# CON_Board_v1.net
KiCad netlist of a schematic drawn in EAGLE
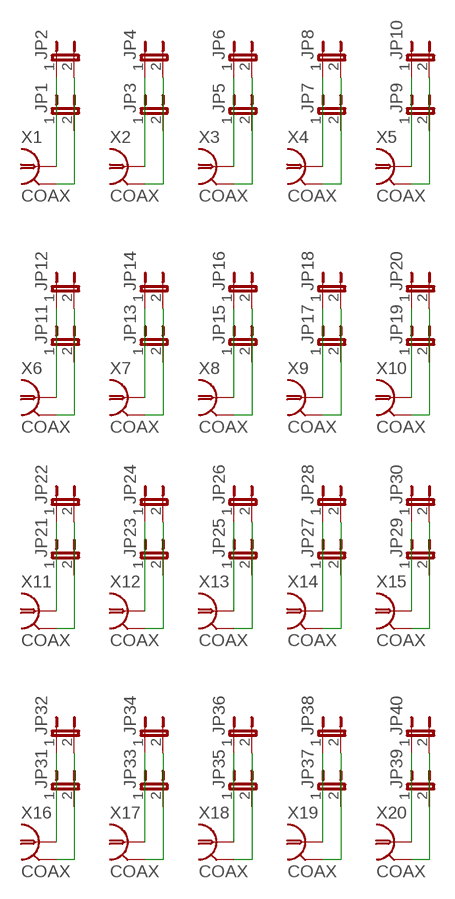
[diagram p0: schematic, sheet 1]

(export (version "E")
  (design (tool "Eeschema 10.0.6"))
  (components
    (comp (ref "JP1")
      (value "JP1E")
      (footprint "eagle-import:JP1")
      (libsource (lib "eagle-import") (part "JP1E"))
    )
    (comp (ref "JP2")
      (value "JP1E")
      (footprint "eagle-import:JP1")
      (libsource (lib "eagle-import") (part "JP1E"))
    )
    (comp (ref "JP3")
      (value "JP1E")
      (footprint "eagle-import:JP1")
      (libsource (lib "eagle-import") (part "JP1E"))
    )
    (comp (ref "JP4")
      (value "JP1E")
      (footprint "eagle-import:JP1")
      (libsource (lib "eagle-import") (part "JP1E"))
    )
    (comp (ref "JP5")
      (value "JP1E")
      (footprint "eagle-import:JP1")
      (libsource (lib "eagle-import") (part "JP1E"))
    )
    (comp (ref "JP6")
      (value "JP1E")
      (footprint "eagle-import:JP1")
      (libsource (lib "eagle-import") (part "JP1E"))
    )
    (comp (ref "JP7")
      (value "JP1E")
      (footprint "eagle-import:JP1")
      (libsource (lib "eagle-import") (part "JP1E"))
    )
    (comp (ref "JP8")
      (value "JP1E")
      (footprint "eagle-import:JP1")
      (libsource (lib "eagle-import") (part "JP1E"))
    )
    (comp (ref "JP9")
      (value "JP1E")
      (footprint "eagle-import:JP1")
      (libsource (lib "eagle-import") (part "JP1E"))
    )
    (comp (ref "JP10")
      (value "JP1E")
      (footprint "eagle-import:JP1")
      (libsource (lib "eagle-import") (part "JP1E"))
    )
    (comp (ref "JP11")
      (value "JP1E")
      (footprint "eagle-import:JP1")
      (libsource (lib "eagle-import") (part "JP1E"))
    )
    (comp (ref "JP12")
      (value "JP1E")
      (footprint "eagle-import:JP1")
      (libsource (lib "eagle-import") (part "JP1E"))
    )
    (comp (ref "JP13")
      (value "JP1E")
      (footprint "eagle-import:JP1")
      (libsource (lib "eagle-import") (part "JP1E"))
    )
    (comp (ref "JP14")
      (value "JP1E")
      (footprint "eagle-import:JP1")
      (libsource (lib "eagle-import") (part "JP1E"))
    )
    (comp (ref "JP15")
      (value "JP1E")
      (footprint "eagle-import:JP1")
      (libsource (lib "eagle-import") (part "JP1E"))
    )
    (comp (ref "JP16")
      (value "JP1E")
      (footprint "eagle-import:JP1")
      (libsource (lib "eagle-import") (part "JP1E"))
    )
    (comp (ref "JP17")
      (value "JP1E")
      (footprint "eagle-import:JP1")
      (libsource (lib "eagle-import") (part "JP1E"))
    )
    (comp (ref "JP18")
      (value "JP1E")
      (footprint "eagle-import:JP1")
      (libsource (lib "eagle-import") (part "JP1E"))
    )
    (comp (ref "JP19")
      (value "JP1E")
      (footprint "eagle-import:JP1")
      (libsource (lib "eagle-import") (part "JP1E"))
    )
    (comp (ref "JP20")
      (value "JP1E")
      (footprint "eagle-import:JP1")
      (libsource (lib "eagle-import") (part "JP1E"))
    )
    (comp (ref "JP21")
      (value "JP1E")
      (footprint "eagle-import:JP1")
      (libsource (lib "eagle-import") (part "JP1E"))
    )
    (comp (ref "JP22")
      (value "JP1E")
      (footprint "eagle-import:JP1")
      (libsource (lib "eagle-import") (part "JP1E"))
    )
    (comp (ref "JP23")
      (value "JP1E")
      (footprint "eagle-import:JP1")
      (libsource (lib "eagle-import") (part "JP1E"))
    )
    (comp (ref "JP24")
      (value "JP1E")
      (footprint "eagle-import:JP1")
      (libsource (lib "eagle-import") (part "JP1E"))
    )
    (comp (ref "JP25")
      (value "JP1E")
      (footprint "eagle-import:JP1")
      (libsource (lib "eagle-import") (part "JP1E"))
    )
    (comp (ref "JP26")
      (value "JP1E")
      (footprint "eagle-import:JP1")
      (libsource (lib "eagle-import") (part "JP1E"))
    )
    (comp (ref "JP27")
      (value "JP1E")
      (footprint "eagle-import:JP1")
      (libsource (lib "eagle-import") (part "JP1E"))
    )
    (comp (ref "JP28")
      (value "JP1E")
      (footprint "eagle-import:JP1")
      (libsource (lib "eagle-import") (part "JP1E"))
    )
    (comp (ref "JP29")
      (value "JP1E")
      (footprint "eagle-import:JP1")
      (libsource (lib "eagle-import") (part "JP1E"))
    )
    (comp (ref "JP30")
      (value "JP1E")
      (footprint "eagle-import:JP1")
      (libsource (lib "eagle-import") (part "JP1E"))
    )
    (comp (ref "JP31")
      (value "JP1E")
      (footprint "eagle-import:JP1")
      (libsource (lib "eagle-import") (part "JP1E"))
    )
    (comp (ref "JP32")
      (value "JP1E")
      (footprint "eagle-import:JP1")
      (libsource (lib "eagle-import") (part "JP1E"))
    )
    (comp (ref "JP33")
      (value "JP1E")
      (footprint "eagle-import:JP1")
      (libsource (lib "eagle-import") (part "JP1E"))
    )
    (comp (ref "JP34")
      (value "JP1E")
      (footprint "eagle-import:JP1")
      (libsource (lib "eagle-import") (part "JP1E"))
    )
    (comp (ref "JP35")
      (value "JP1E")
      (footprint "eagle-import:JP1")
      (libsource (lib "eagle-import") (part "JP1E"))
    )
    (comp (ref "JP36")
      (value "JP1E")
      (footprint "eagle-import:JP1")
      (libsource (lib "eagle-import") (part "JP1E"))
    )
    (comp (ref "JP37")
      (value "JP1E")
      (footprint "eagle-import:JP1")
      (libsource (lib "eagle-import") (part "JP1E"))
    )
    (comp (ref "JP38")
      (value "JP1E")
      (footprint "eagle-import:JP1")
      (libsource (lib "eagle-import") (part "JP1E"))
    )
    (comp (ref "JP39")
      (value "JP1E")
      (footprint "eagle-import:JP1")
      (libsource (lib "eagle-import") (part "JP1E"))
    )
    (comp (ref "JP40")
      (value "JP1E")
      (footprint "eagle-import:JP1")
      (libsource (lib "eagle-import") (part "JP1E"))
    )
    (comp (ref "X1")
      (value "COAX")
      (footprint "eagle-import:31-5329")
      (libsource (lib "eagle-import") (part "31-5329-52RFX31-5329-52RFX"))
    )
    (comp (ref "X2")
      (value "COAX")
      (footprint "eagle-import:31-5329")
      (libsource (lib "eagle-import") (part "31-5329-52RFX31-5329-52RFX"))
    )
    (comp (ref "X3")
      (value "COAX")
      (footprint "eagle-import:31-5329")
      (libsource (lib "eagle-import") (part "31-5329-52RFX31-5329-52RFX"))
    )
    (comp (ref "X4")
      (value "COAX")
      (footprint "eagle-import:31-5329")
      (libsource (lib "eagle-import") (part "31-5329-52RFX31-5329-52RFX"))
    )
    (comp (ref "X5")
      (value "COAX")
      (footprint "eagle-import:31-5329")
      (libsource (lib "eagle-import") (part "31-5329-52RFX31-5329-52RFX"))
    )
    (comp (ref "X6")
      (value "COAX")
      (footprint "eagle-import:31-5329")
      (libsource (lib "eagle-import") (part "31-5329-52RFX31-5329-52RFX"))
    )
    (comp (ref "X7")
      (value "COAX")
      (footprint "eagle-import:31-5329")
      (libsource (lib "eagle-import") (part "31-5329-52RFX31-5329-52RFX"))
    )
    (comp (ref "X8")
      (value "COAX")
      (footprint "eagle-import:31-5329")
      (libsource (lib "eagle-import") (part "31-5329-52RFX31-5329-52RFX"))
    )
    (comp (ref "X9")
      (value "COAX")
      (footprint "eagle-import:31-5329")
      (libsource (lib "eagle-import") (part "31-5329-52RFX31-5329-52RFX"))
    )
    (comp (ref "X10")
      (value "COAX")
      (footprint "eagle-import:31-5329")
      (libsource (lib "eagle-import") (part "31-5329-52RFX31-5329-52RFX"))
    )
    (comp (ref "X11")
      (value "COAX")
      (footprint "eagle-import:31-5329")
      (libsource (lib "eagle-import") (part "31-5329-52RFX31-5329-52RFX"))
    )
    (comp (ref "X12")
      (value "COAX")
      (footprint "eagle-import:31-5329")
      (libsource (lib "eagle-import") (part "31-5329-52RFX31-5329-52RFX"))
    )
    (comp (ref "X13")
      (value "COAX")
      (footprint "eagle-import:31-5329")
      (libsource (lib "eagle-import") (part "31-5329-52RFX31-5329-52RFX"))
    )
    (comp (ref "X14")
      (value "COAX")
      (footprint "eagle-import:31-5329")
      (libsource (lib "eagle-import") (part "31-5329-52RFX31-5329-52RFX"))
    )
    (comp (ref "X15")
      (value "COAX")
      (footprint "eagle-import:31-5329")
      (libsource (lib "eagle-import") (part "31-5329-52RFX31-5329-52RFX"))
    )
    (comp (ref "X16")
      (value "COAX")
      (footprint "eagle-import:31-5329")
      (libsource (lib "eagle-import") (part "31-5329-52RFX31-5329-52RFX"))
    )
    (comp (ref "X17")
      (value "COAX")
      (footprint "eagle-import:31-5329")
      (libsource (lib "eagle-import") (part "31-5329-52RFX31-5329-52RFX"))
    )
    (comp (ref "X18")
      (value "COAX")
      (footprint "eagle-import:31-5329")
      (libsource (lib "eagle-import") (part "31-5329-52RFX31-5329-52RFX"))
    )
    (comp (ref "X19")
      (value "COAX")
      (footprint "eagle-import:31-5329")
      (libsource (lib "eagle-import") (part "31-5329-52RFX31-5329-52RFX"))
    )
    (comp (ref "X20")
      (value "COAX")
      (footprint "eagle-import:31-5329")
      (libsource (lib "eagle-import") (part "31-5329-52RFX31-5329-52RFX"))
    )
  )
  (nets
    (net (code "1") (name "Net-(JP1-Pad1)") (class "Default")
      (node (ref "JP1") (pin "1") (pinfunction "1_1") (pintype "passive"))
      (node (ref "JP2") (pin "1") (pinfunction "1_1") (pintype "passive"))
      (node (ref "X1") (pin "1") (pinfunction "1_1") (pintype "passive"))
    )
    (net (code "2") (name "Net-(JP1-Pad2)") (class "Default")
      (node (ref "JP1") (pin "2") (pinfunction "2_2") (pintype "passive"))
      (node (ref "JP2") (pin "2") (pinfunction "2_2") (pintype "passive"))
      (node (ref "X1") (pin "2") (pinfunction "2_2") (pintype "passive"))
      (node (ref "X1") (pin "3") (pinfunction "2_3") (pintype "passive"))
      (node (ref "X1") (pin "4") (pinfunction "2_4") (pintype "passive"))
      (node (ref "X1") (pin "5") (pinfunction "2_5") (pintype "passive"))
    )
    (net (code "3") (name "Net-(JP3-Pad1)") (class "Default")
      (node (ref "JP3") (pin "1") (pinfunction "1_1") (pintype "passive"))
      (node (ref "JP4") (pin "1") (pinfunction "1_1") (pintype "passive"))
      (node (ref "X2") (pin "1") (pinfunction "1_1") (pintype "passive"))
    )
    (net (code "4") (name "Net-(JP3-Pad2)") (class "Default")
      (node (ref "JP3") (pin "2") (pinfunction "2_2") (pintype "passive"))
      (node (ref "JP4") (pin "2") (pinfunction "2_2") (pintype "passive"))
      (node (ref "X2") (pin "2") (pinfunction "2_2") (pintype "passive"))
      (node (ref "X2") (pin "3") (pinfunction "2_3") (pintype "passive"))
      (node (ref "X2") (pin "4") (pinfunction "2_4") (pintype "passive"))
      (node (ref "X2") (pin "5") (pinfunction "2_5") (pintype "passive"))
    )
    (net (code "5") (name "Net-(JP5-Pad1)") (class "Default")
      (node (ref "JP5") (pin "1") (pinfunction "1_1") (pintype "passive"))
      (node (ref "JP6") (pin "1") (pinfunction "1_1") (pintype "passive"))
      (node (ref "X3") (pin "1") (pinfunction "1_1") (pintype "passive"))
    )
    (net (code "6") (name "Net-(JP5-Pad2)") (class "Default")
      (node (ref "JP5") (pin "2") (pinfunction "2_2") (pintype "passive"))
      (node (ref "JP6") (pin "2") (pinfunction "2_2") (pintype "passive"))
      (node (ref "X3") (pin "2") (pinfunction "2_2") (pintype "passive"))
      (node (ref "X3") (pin "3") (pinfunction "2_3") (pintype "passive"))
      (node (ref "X3") (pin "4") (pinfunction "2_4") (pintype "passive"))
      (node (ref "X3") (pin "5") (pinfunction "2_5") (pintype "passive"))
    )
    (net (code "7") (name "Net-(JP7-Pad1)") (class "Default")
      (node (ref "JP7") (pin "1") (pinfunction "1_1") (pintype "passive"))
      (node (ref "JP8") (pin "1") (pinfunction "1_1") (pintype "passive"))
      (node (ref "X4") (pin "1") (pinfunction "1_1") (pintype "passive"))
    )
    (net (code "8") (name "Net-(JP7-Pad2)") (class "Default")
      (node (ref "JP7") (pin "2") (pinfunction "2_2") (pintype "passive"))
      (node (ref "JP8") (pin "2") (pinfunction "2_2") (pintype "passive"))
      (node (ref "X4") (pin "2") (pinfunction "2_2") (pintype "passive"))
      (node (ref "X4") (pin "3") (pinfunction "2_3") (pintype "passive"))
      (node (ref "X4") (pin "4") (pinfunction "2_4") (pintype "passive"))
      (node (ref "X4") (pin "5") (pinfunction "2_5") (pintype "passive"))
    )
    (net (code "9") (name "Net-(JP10-Pad1)") (class "Default")
      (node (ref "JP10") (pin "1") (pinfunction "1_1") (pintype "passive"))
      (node (ref "JP9") (pin "1") (pinfunction "1_1") (pintype "passive"))
      (node (ref "X5") (pin "1") (pinfunction "1_1") (pintype "passive"))
    )
    (net (code "10") (name "Net-(JP10-Pad2)") (class "Default")
      (node (ref "JP10") (pin "2") (pinfunction "2_2") (pintype "passive"))
      (node (ref "JP9") (pin "2") (pinfunction "2_2") (pintype "passive"))
      (node (ref "X5") (pin "2") (pinfunction "2_2") (pintype "passive"))
      (node (ref "X5") (pin "3") (pinfunction "2_3") (pintype "passive"))
      (node (ref "X5") (pin "4") (pinfunction "2_4") (pintype "passive"))
      (node (ref "X5") (pin "5") (pinfunction "2_5") (pintype "passive"))
    )
    (net (code "11") (name "Net-(JP11-Pad1)") (class "Default")
      (node (ref "JP11") (pin "1") (pinfunction "1_1") (pintype "passive"))
      (node (ref "JP12") (pin "1") (pinfunction "1_1") (pintype "passive"))
      (node (ref "X6") (pin "1") (pinfunction "1_1") (pintype "passive"))
    )
    (net (code "12") (name "Net-(JP11-Pad2)") (class "Default")
      (node (ref "JP11") (pin "2") (pinfunction "2_2") (pintype "passive"))
      (node (ref "JP12") (pin "2") (pinfunction "2_2") (pintype "passive"))
      (node (ref "X6") (pin "2") (pinfunction "2_2") (pintype "passive"))
      (node (ref "X6") (pin "3") (pinfunction "2_3") (pintype "passive"))
      (node (ref "X6") (pin "4") (pinfunction "2_4") (pintype "passive"))
      (node (ref "X6") (pin "5") (pinfunction "2_5") (pintype "passive"))
    )
    (net (code "13") (name "Net-(JP13-Pad1)") (class "Default")
      (node (ref "JP13") (pin "1") (pinfunction "1_1") (pintype "passive"))
      (node (ref "JP14") (pin "1") (pinfunction "1_1") (pintype "passive"))
      (node (ref "X7") (pin "1") (pinfunction "1_1") (pintype "passive"))
    )
    (net (code "14") (name "Net-(JP13-Pad2)") (class "Default")
      (node (ref "JP13") (pin "2") (pinfunction "2_2") (pintype "passive"))
      (node (ref "JP14") (pin "2") (pinfunction "2_2") (pintype "passive"))
      (node (ref "X7") (pin "2") (pinfunction "2_2") (pintype "passive"))
      (node (ref "X7") (pin "3") (pinfunction "2_3") (pintype "passive"))
      (node (ref "X7") (pin "4") (pinfunction "2_4") (pintype "passive"))
      (node (ref "X7") (pin "5") (pinfunction "2_5") (pintype "passive"))
    )
    (net (code "15") (name "Net-(JP15-Pad1)") (class "Default")
      (node (ref "JP15") (pin "1") (pinfunction "1_1") (pintype "passive"))
      (node (ref "JP16") (pin "1") (pinfunction "1_1") (pintype "passive"))
      (node (ref "X8") (pin "1") (pinfunction "1_1") (pintype "passive"))
    )
    (net (code "16") (name "Net-(JP15-Pad2)") (class "Default")
      (node (ref "JP15") (pin "2") (pinfunction "2_2") (pintype "passive"))
      (node (ref "JP16") (pin "2") (pinfunction "2_2") (pintype "passive"))
      (node (ref "X8") (pin "2") (pinfunction "2_2") (pintype "passive"))
      (node (ref "X8") (pin "3") (pinfunction "2_3") (pintype "passive"))
      (node (ref "X8") (pin "4") (pinfunction "2_4") (pintype "passive"))
      (node (ref "X8") (pin "5") (pinfunction "2_5") (pintype "passive"))
    )
    (net (code "17") (name "Net-(JP17-Pad1)") (class "Default")
      (node (ref "JP17") (pin "1") (pinfunction "1_1") (pintype "passive"))
      (node (ref "JP18") (pin "1") (pinfunction "1_1") (pintype "passive"))
      (node (ref "X9") (pin "1") (pinfunction "1_1") (pintype "passive"))
    )
    (net (code "18") (name "Net-(JP17-Pad2)") (class "Default")
      (node (ref "JP17") (pin "2") (pinfunction "2_2") (pintype "passive"))
      (node (ref "JP18") (pin "2") (pinfunction "2_2") (pintype "passive"))
      (node (ref "X9") (pin "2") (pinfunction "2_2") (pintype "passive"))
      (node (ref "X9") (pin "3") (pinfunction "2_3") (pintype "passive"))
      (node (ref "X9") (pin "4") (pinfunction "2_4") (pintype "passive"))
      (node (ref "X9") (pin "5") (pinfunction "2_5") (pintype "passive"))
    )
    (net (code "19") (name "Net-(JP19-Pad1)") (class "Default")
      (node (ref "JP19") (pin "1") (pinfunction "1_1") (pintype "passive"))
      (node (ref "JP20") (pin "1") (pinfunction "1_1") (pintype "passive"))
      (node (ref "X10") (pin "1") (pinfunction "1_1") (pintype "passive"))
    )
    (net (code "20") (name "Net-(JP19-Pad2)") (class "Default")
      (node (ref "JP19") (pin "2") (pinfunction "2_2") (pintype "passive"))
      (node (ref "JP20") (pin "2") (pinfunction "2_2") (pintype "passive"))
      (node (ref "X10") (pin "2") (pinfunction "2_2") (pintype "passive"))
      (node (ref "X10") (pin "3") (pinfunction "2_3") (pintype "passive"))
      (node (ref "X10") (pin "4") (pinfunction "2_4") (pintype "passive"))
      (node (ref "X10") (pin "5") (pinfunction "2_5") (pintype "passive"))
    )
    (net (code "21") (name "Net-(JP21-Pad1)") (class "Default")
      (node (ref "JP21") (pin "1") (pinfunction "1_1") (pintype "passive"))
      (node (ref "JP22") (pin "1") (pinfunction "1_1") (pintype "passive"))
      (node (ref "X11") (pin "1") (pinfunction "1_1") (pintype "passive"))
    )
    (net (code "22") (name "Net-(JP21-Pad2)") (class "Default")
      (node (ref "JP21") (pin "2") (pinfunction "2_2") (pintype "passive"))
      (node (ref "JP22") (pin "2") (pinfunction "2_2") (pintype "passive"))
      (node (ref "X11") (pin "2") (pinfunction "2_2") (pintype "passive"))
      (node (ref "X11") (pin "3") (pinfunction "2_3") (pintype "passive"))
      (node (ref "X11") (pin "4") (pinfunction "2_4") (pintype "passive"))
      (node (ref "X11") (pin "5") (pinfunction "2_5") (pintype "passive"))
    )
    (net (code "23") (name "Net-(JP23-Pad1)") (class "Default")
      (node (ref "JP23") (pin "1") (pinfunction "1_1") (pintype "passive"))
      (node (ref "JP24") (pin "1") (pinfunction "1_1") (pintype "passive"))
      (node (ref "X12") (pin "1") (pinfunction "1_1") (pintype "passive"))
    )
    (net (code "24") (name "Net-(JP23-Pad2)") (class "Default")
      (node (ref "JP23") (pin "2") (pinfunction "2_2") (pintype "passive"))
      (node (ref "JP24") (pin "2") (pinfunction "2_2") (pintype "passive"))
      (node (ref "X12") (pin "2") (pinfunction "2_2") (pintype "passive"))
      (node (ref "X12") (pin "3") (pinfunction "2_3") (pintype "passive"))
      (node (ref "X12") (pin "4") (pinfunction "2_4") (pintype "passive"))
      (node (ref "X12") (pin "5") (pinfunction "2_5") (pintype "passive"))
    )
    (net (code "25") (name "Net-(JP25-Pad1)") (class "Default")
      (node (ref "JP25") (pin "1") (pinfunction "1_1") (pintype "passive"))
      (node (ref "JP26") (pin "1") (pinfunction "1_1") (pintype "passive"))
      (node (ref "X13") (pin "1") (pinfunction "1_1") (pintype "passive"))
    )
    (net (code "26") (name "Net-(JP25-Pad2)") (class "Default")
      (node (ref "JP25") (pin "2") (pinfunction "2_2") (pintype "passive"))
      (node (ref "JP26") (pin "2") (pinfunction "2_2") (pintype "passive"))
      (node (ref "X13") (pin "2") (pinfunction "2_2") (pintype "passive"))
      (node (ref "X13") (pin "3") (pinfunction "2_3") (pintype "passive"))
      (node (ref "X13") (pin "4") (pinfunction "2_4") (pintype "passive"))
      (node (ref "X13") (pin "5") (pinfunction "2_5") (pintype "passive"))
    )
    (net (code "27") (name "Net-(JP27-Pad1)") (class "Default")
      (node (ref "JP27") (pin "1") (pinfunction "1_1") (pintype "passive"))
      (node (ref "JP28") (pin "1") (pinfunction "1_1") (pintype "passive"))
      (node (ref "X14") (pin "1") (pinfunction "1_1") (pintype "passive"))
    )
    (net (code "28") (name "Net-(JP27-Pad2)") (class "Default")
      (node (ref "JP27") (pin "2") (pinfunction "2_2") (pintype "passive"))
      (node (ref "JP28") (pin "2") (pinfunction "2_2") (pintype "passive"))
      (node (ref "X14") (pin "2") (pinfunction "2_2") (pintype "passive"))
      (node (ref "X14") (pin "3") (pinfunction "2_3") (pintype "passive"))
      (node (ref "X14") (pin "4") (pinfunction "2_4") (pintype "passive"))
      (node (ref "X14") (pin "5") (pinfunction "2_5") (pintype "passive"))
    )
    (net (code "29") (name "Net-(JP29-Pad1)") (class "Default")
      (node (ref "JP29") (pin "1") (pinfunction "1_1") (pintype "passive"))
      (node (ref "JP30") (pin "1") (pinfunction "1_1") (pintype "passive"))
      (node (ref "X15") (pin "1") (pinfunction "1_1") (pintype "passive"))
    )
    (net (code "30") (name "Net-(JP29-Pad2)") (class "Default")
      (node (ref "JP29") (pin "2") (pinfunction "2_2") (pintype "passive"))
      (node (ref "JP30") (pin "2") (pinfunction "2_2") (pintype "passive"))
      (node (ref "X15") (pin "2") (pinfunction "2_2") (pintype "passive"))
      (node (ref "X15") (pin "3") (pinfunction "2_3") (pintype "passive"))
      (node (ref "X15") (pin "4") (pinfunction "2_4") (pintype "passive"))
      (node (ref "X15") (pin "5") (pinfunction "2_5") (pintype "passive"))
    )
    (net (code "31") (name "Net-(JP31-Pad1)") (class "Default")
      (node (ref "JP31") (pin "1") (pinfunction "1_1") (pintype "passive"))
      (node (ref "JP32") (pin "1") (pinfunction "1_1") (pintype "passive"))
      (node (ref "X16") (pin "1") (pinfunction "1_1") (pintype "passive"))
    )
    (net (code "32") (name "Net-(JP31-Pad2)") (class "Default")
      (node (ref "JP31") (pin "2") (pinfunction "2_2") (pintype "passive"))
      (node (ref "JP32") (pin "2") (pinfunction "2_2") (pintype "passive"))
      (node (ref "X16") (pin "2") (pinfunction "2_2") (pintype "passive"))
      (node (ref "X16") (pin "3") (pinfunction "2_3") (pintype "passive"))
      (node (ref "X16") (pin "4") (pinfunction "2_4") (pintype "passive"))
      (node (ref "X16") (pin "5") (pinfunction "2_5") (pintype "passive"))
    )
    (net (code "33") (name "Net-(JP33-Pad1)") (class "Default")
      (node (ref "JP33") (pin "1") (pinfunction "1_1") (pintype "passive"))
      (node (ref "JP34") (pin "1") (pinfunction "1_1") (pintype "passive"))
      (node (ref "X17") (pin "1") (pinfunction "1_1") (pintype "passive"))
    )
    (net (code "34") (name "Net-(JP33-Pad2)") (class "Default")
      (node (ref "JP33") (pin "2") (pinfunction "2_2") (pintype "passive"))
      (node (ref "JP34") (pin "2") (pinfunction "2_2") (pintype "passive"))
      (node (ref "X17") (pin "2") (pinfunction "2_2") (pintype "passive"))
      (node (ref "X17") (pin "3") (pinfunction "2_3") (pintype "passive"))
      (node (ref "X17") (pin "4") (pinfunction "2_4") (pintype "passive"))
      (node (ref "X17") (pin "5") (pinfunction "2_5") (pintype "passive"))
    )
    (net (code "35") (name "Net-(JP35-Pad1)") (class "Default")
      (node (ref "JP35") (pin "1") (pinfunction "1_1") (pintype "passive"))
      (node (ref "JP36") (pin "1") (pinfunction "1_1") (pintype "passive"))
      (node (ref "X18") (pin "1") (pinfunction "1_1") (pintype "passive"))
    )
    (net (code "36") (name "Net-(JP35-Pad2)") (class "Default")
      (node (ref "JP35") (pin "2") (pinfunction "2_2") (pintype "passive"))
      (node (ref "JP36") (pin "2") (pinfunction "2_2") (pintype "passive"))
      (node (ref "X18") (pin "2") (pinfunction "2_2") (pintype "passive"))
      (node (ref "X18") (pin "3") (pinfunction "2_3") (pintype "passive"))
      (node (ref "X18") (pin "4") (pinfunction "2_4") (pintype "passive"))
      (node (ref "X18") (pin "5") (pinfunction "2_5") (pintype "passive"))
    )
    (net (code "37") (name "Net-(JP37-Pad1)") (class "Default")
      (node (ref "JP37") (pin "1") (pinfunction "1_1") (pintype "passive"))
      (node (ref "JP38") (pin "1") (pinfunction "1_1") (pintype "passive"))
      (node (ref "X19") (pin "1") (pinfunction "1_1") (pintype "passive"))
    )
    (net (code "38") (name "Net-(JP37-Pad2)") (class "Default")
      (node (ref "JP37") (pin "2") (pinfunction "2_2") (pintype "passive"))
      (node (ref "JP38") (pin "2") (pinfunction "2_2") (pintype "passive"))
      (node (ref "X19") (pin "2") (pinfunction "2_2") (pintype "passive"))
      (node (ref "X19") (pin "3") (pinfunction "2_3") (pintype "passive"))
      (node (ref "X19") (pin "4") (pinfunction "2_4") (pintype "passive"))
      (node (ref "X19") (pin "5") (pinfunction "2_5") (pintype "passive"))
    )
    (net (code "39") (name "Net-(JP39-Pad1)") (class "Default")
      (node (ref "JP39") (pin "1") (pinfunction "1_1") (pintype "passive"))
      (node (ref "JP40") (pin "1") (pinfunction "1_1") (pintype "passive"))
      (node (ref "X20") (pin "1") (pinfunction "1_1") (pintype "passive"))
    )
    (net (code "40") (name "Net-(JP39-Pad2)") (class "Default")
      (node (ref "JP39") (pin "2") (pinfunction "2_2") (pintype "passive"))
      (node (ref "JP40") (pin "2") (pinfunction "2_2") (pintype "passive"))
      (node (ref "X20") (pin "2") (pinfunction "2_2") (pintype "passive"))
      (node (ref "X20") (pin "3") (pinfunction "2_3") (pintype "passive"))
      (node (ref "X20") (pin "4") (pinfunction "2_4") (pintype "passive"))
      (node (ref "X20") (pin "5") (pinfunction "2_5") (pintype "passive"))
    )
  )
)
